# car_board_ver1.net
KiCad netlist of a schematic drawn in Altium Designer
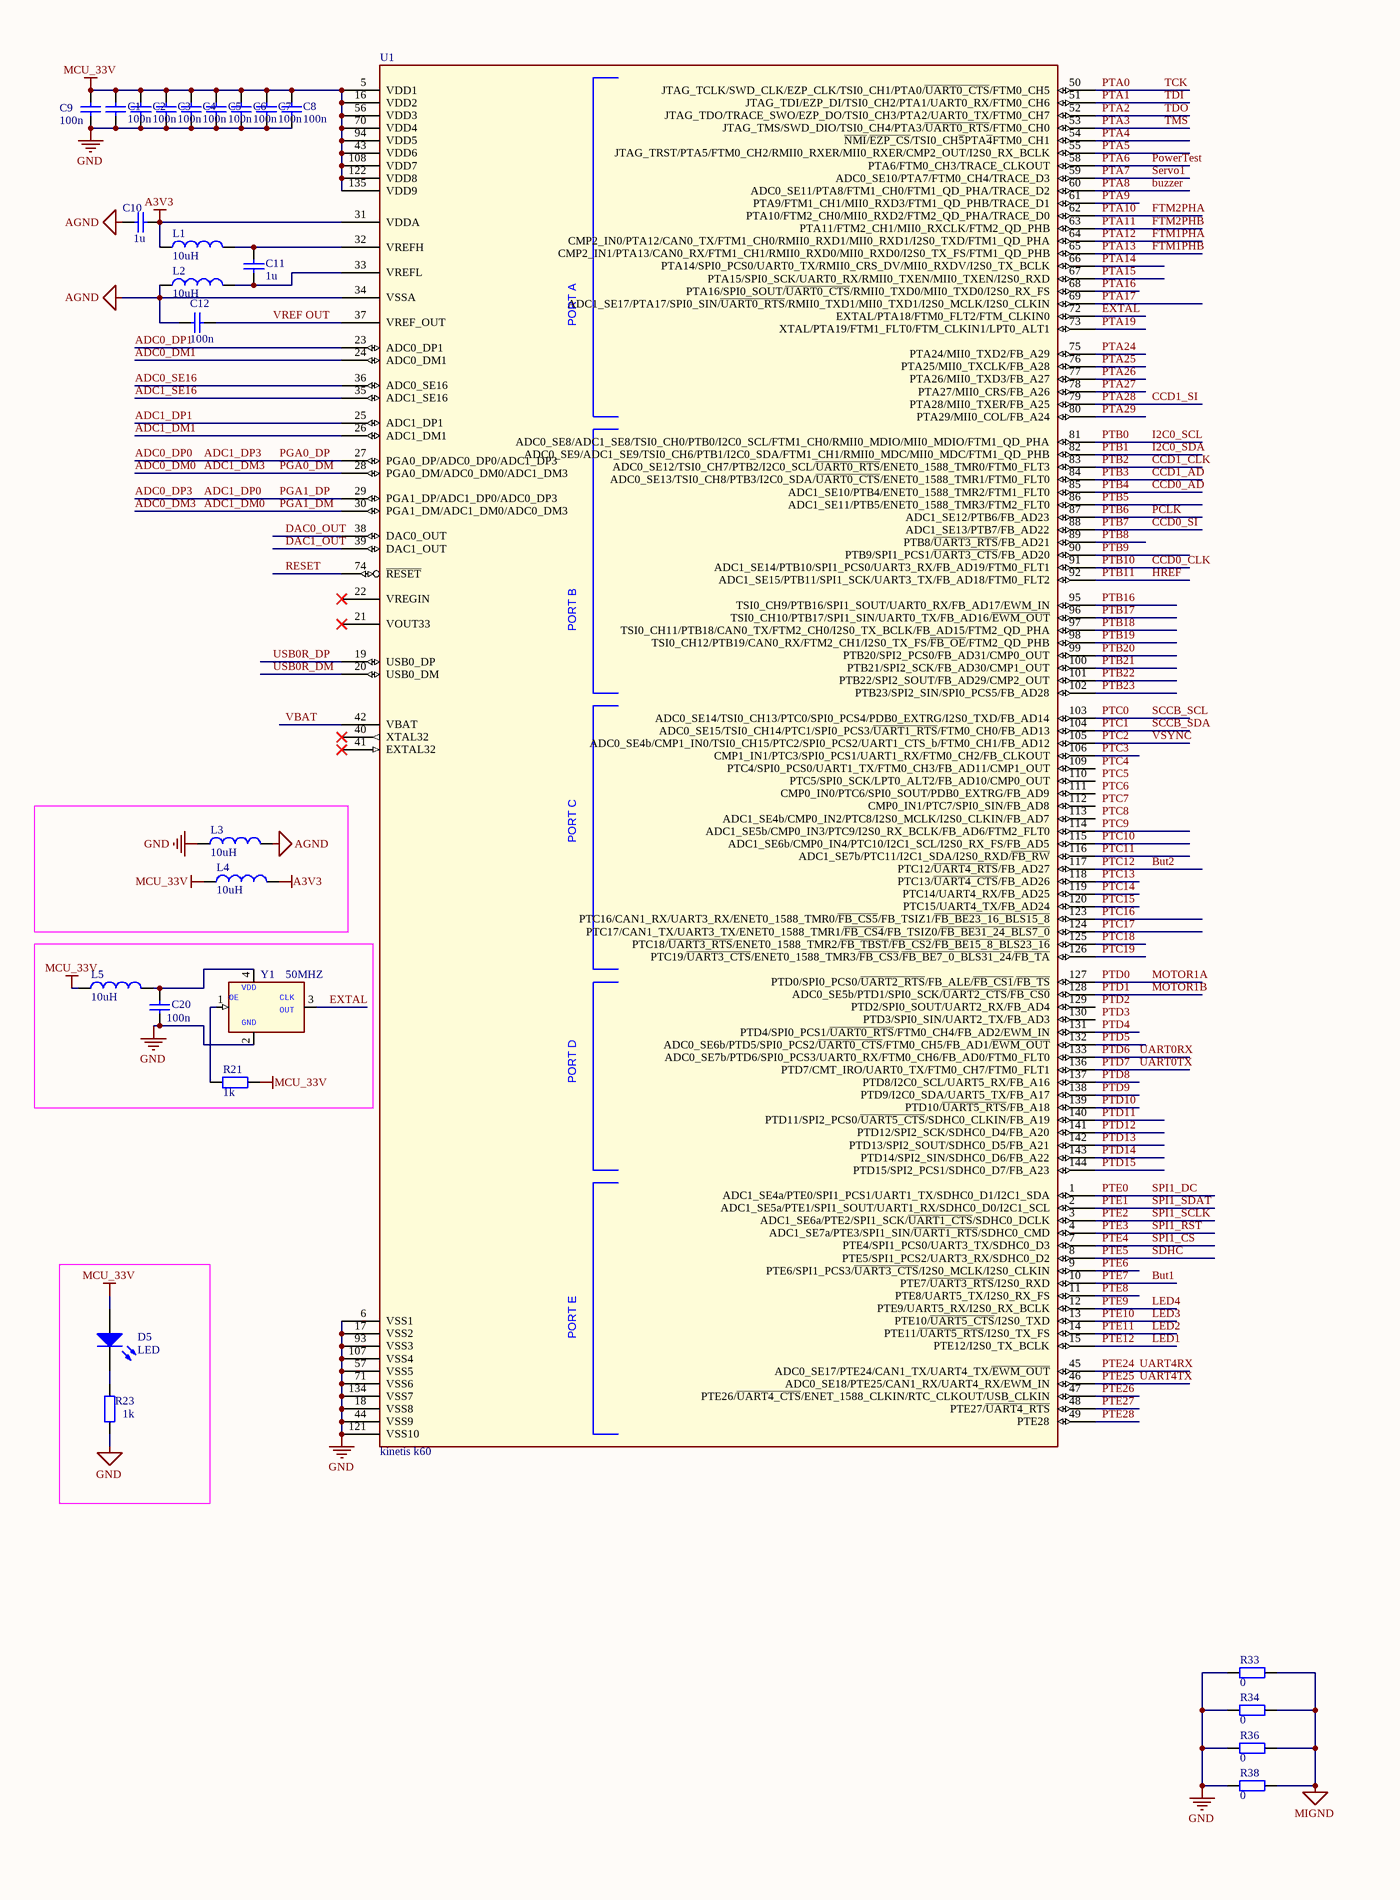
[diagram p0: car board ver1.SchDoc, left]
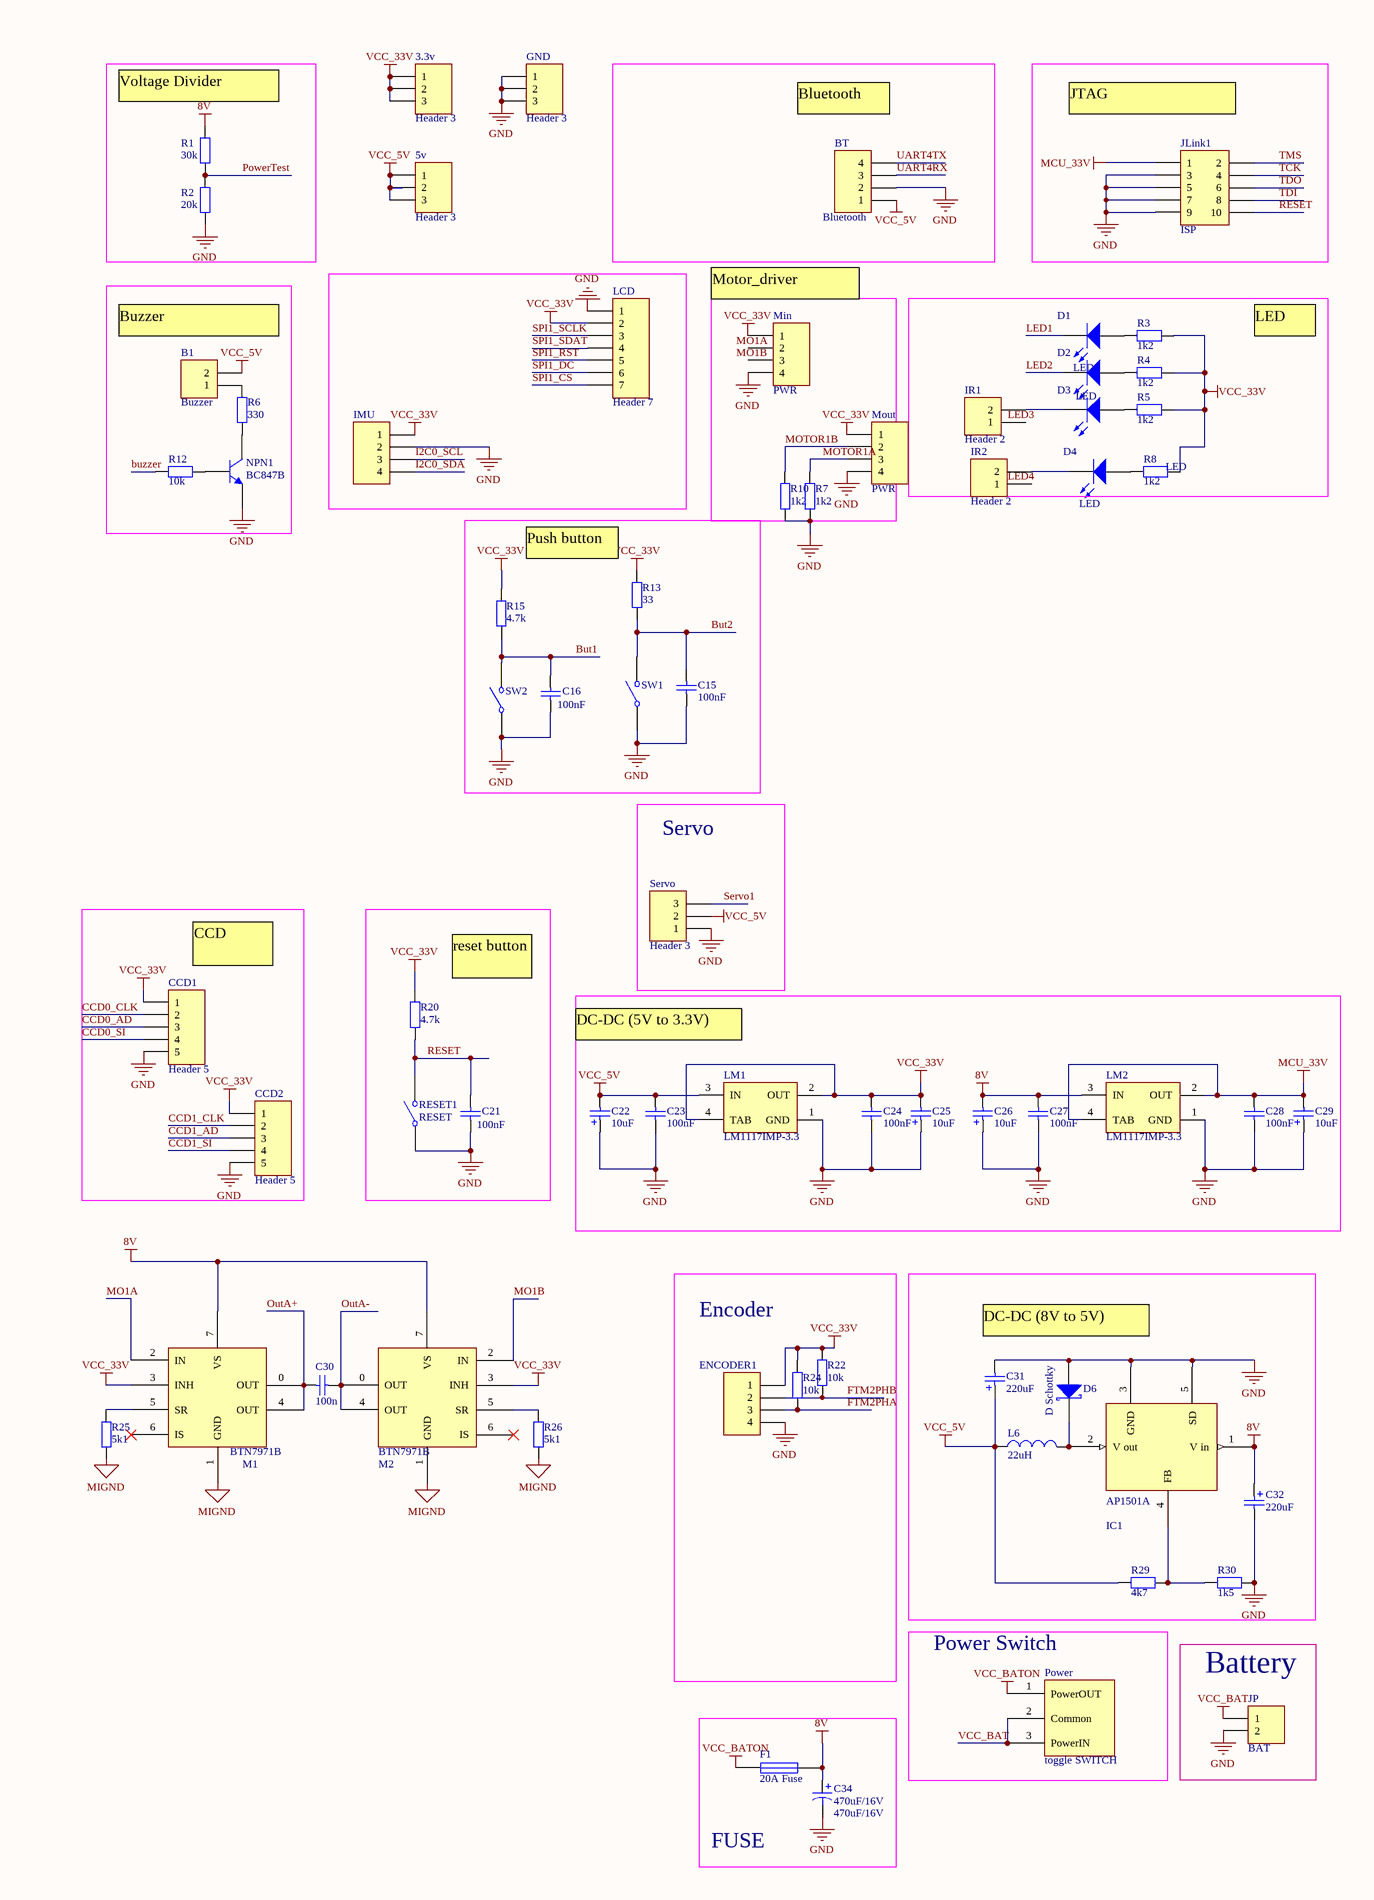
[diagram p1: car board ver1.SchDoc, right]

(export (version "E")
  (design (tool "Eeschema 10.0.6"))
  (components
    (comp (ref "3.3v")
      (value "Header 3")
      (footprint "HDR1X3")
      (description "Header, 3-Pin")
      (fields (field (name "PUBLISHER") "Altium Limited"))
      (libsource (lib "SmartCar2015_Connectors") (part "Header 3"))
    )
    (comp (ref "5v")
      (value "Header 3")
      (footprint "HDR1X3")
      (description "Header, 3-Pin")
      (fields (field (name "PUBLISHER") "Altium Limited"))
      (libsource (lib "SmartCar2015_Connectors") (part "Header 3"))
    )
    (comp (ref "B1")
      (value "Buzzer")
      (footprint "Buzzer")
      (libsource (lib "SmartCar2015_RCL") (part "Buzzer"))
    )
    (comp (ref "BT")
      (value "Bluetooth")
      (footprint "6410-04")
      (description "Header, 4-Pin")
      (fields (field (name "PUBLISHER") "Altium Limited"))
      (libsource (lib "") (part "Header 4_2"))
    )
    (comp (ref "C1")
      (value "100n")
      (footprint "CC2012-0805")
      (description "Capacitor (Semiconductor SIM Model)")
      (fields (field (name "PUBLISHER") "Altium Limited"))
      (libsource (lib "SmartCar2015_RCL") (part "Cap Semi"))
    )
    (comp (ref "C2")
      (value "100n")
      (footprint "CC2012-0805")
      (description "Capacitor (Semiconductor SIM Model)")
      (fields (field (name "PUBLISHER") "Altium Limited"))
      (libsource (lib "SmartCar2015_RCL") (part "Cap Semi"))
    )
    (comp (ref "C3")
      (value "100n")
      (footprint "CC2012-0805")
      (description "Capacitor (Semiconductor SIM Model)")
      (fields (field (name "PUBLISHER") "Altium Limited"))
      (libsource (lib "SmartCar2015_RCL") (part "Cap Semi"))
    )
    (comp (ref "C4")
      (value "100n")
      (footprint "CC2012-0805")
      (description "Capacitor (Semiconductor SIM Model)")
      (fields (field (name "PUBLISHER") "Altium Limited"))
      (libsource (lib "SmartCar2015_RCL") (part "Cap Semi"))
    )
    (comp (ref "C5")
      (value "100n")
      (footprint "CC2012-0805")
      (description "Capacitor (Semiconductor SIM Model)")
      (fields (field (name "PUBLISHER") "Altium Limited"))
      (libsource (lib "SmartCar2015_RCL") (part "Cap Semi"))
    )
    (comp (ref "C6")
      (value "100n")
      (footprint "CC2012-0805")
      (description "Capacitor (Semiconductor SIM Model)")
      (fields (field (name "PUBLISHER") "Altium Limited"))
      (libsource (lib "SmartCar2015_RCL") (part "Cap Semi"))
    )
    (comp (ref "C7")
      (value "100n")
      (footprint "CC2012-0805")
      (description "Capacitor (Semiconductor SIM Model)")
      (fields (field (name "PUBLISHER") "Altium Limited"))
      (libsource (lib "SmartCar2015_RCL") (part "Cap Semi"))
    )
    (comp (ref "C8")
      (value "100n")
      (footprint "CC2012-0805")
      (description "Capacitor (Semiconductor SIM Model)")
      (fields (field (name "PUBLISHER") "Altium Limited"))
      (libsource (lib "SmartCar2015_RCL") (part "Cap Semi"))
    )
    (comp (ref "C9")
      (value "100n")
      (footprint "CC2012-0805")
      (description "Capacitor (Semiconductor SIM Model)")
      (fields (field (name "PUBLISHER") "Altium Limited"))
      (libsource (lib "SmartCar2015_RCL") (part "Cap Semi"))
    )
    (comp (ref "C10")
      (value "1u")
      (footprint "CC2012-0805")
      (description "Capacitor (Semiconductor SIM Model)")
      (fields (field (name "PUBLISHER") "Altium Limited"))
      (libsource (lib "SmartCar2015_RCL") (part "Cap Semi"))
    )
    (comp (ref "C11")
      (value "1u")
      (footprint "CC2012-0805")
      (description "Capacitor (Semiconductor SIM Model)")
      (fields (field (name "PUBLISHER") "Altium Limited"))
      (libsource (lib "SmartCar2015_RCL") (part "Cap Semi"))
    )
    (comp (ref "C12")
      (value "100n")
      (footprint "CC2012-0805")
      (description "Capacitor (Semiconductor SIM Model)")
      (fields (field (name "PUBLISHER") "Altium Limited"))
      (libsource (lib "SmartCar2015_RCL") (part "Cap Semi"))
    )
    (comp (ref "C15")
      (value "100nF")
      (footprint "CC2012-0805")
      (description "Capacitor (Semiconductor SIM Model)")
      (fields (field (name "PUBLISHER") "Altium Limited"))
      (libsource (lib "SmartCar2015_RCL") (part "Cap Semi"))
    )
    (comp (ref "C16")
      (value "100nF")
      (footprint "CC2012-0805")
      (description "Capacitor (Semiconductor SIM Model)")
      (fields (field (name "PUBLISHER") "Altium Limited"))
      (libsource (lib "SmartCar2015_RCL") (part "Cap Semi"))
    )
    (comp (ref "C20")
      (value "100n")
      (footprint "CC2012-0805")
      (description "Capacitor (Semiconductor SIM Model)")
      (fields (field (name "PUBLISHER") "Altium Limited"))
      (libsource (lib "SmartCar2015_RCL") (part "Cap Semi"))
    )
    (comp (ref "C21")
      (value "100nF")
      (footprint "CC2012-0805")
      (description "Capacitor (Semiconductor SIM Model)")
      (fields (field (name "PUBLISHER") "Altium Limited"))
      (libsource (lib "SmartCar2015_RCL") (part "Cap Semi"))
    )
    (comp (ref "C22")
      (value "10uF")
      (footprint "CC2012-0805")
      (description "Polarized Capacitor (Surface Mount)")
      (fields (field (name "PUBLISHER") "Altium Limited"))
      (libsource (lib "SmartCar2015_RCL") (part "Cap Pol3"))
    )
    (comp (ref "C23")
      (value "100nF")
      (footprint "CC2012-0805")
      (description "Capacitor (Semiconductor SIM Model)")
      (fields (field (name "PUBLISHER") "Altium Limited"))
      (libsource (lib "SmartCar2015_RCL") (part "Cap Semi"))
    )
    (comp (ref "C24")
      (value "100nF")
      (footprint "CC2012-0805")
      (description "Capacitor (Semiconductor SIM Model)")
      (fields (field (name "PUBLISHER") "Altium Limited"))
      (libsource (lib "SmartCar2015_RCL") (part "Cap Semi"))
    )
    (comp (ref "C25")
      (value "10uF")
      (footprint "CC2012-0805")
      (description "Polarized Capacitor (Surface Mount)")
      (fields (field (name "PUBLISHER") "Altium Limited"))
      (libsource (lib "SmartCar2015_RCL") (part "Cap Pol3"))
    )
    (comp (ref "C26")
      (value "10uF")
      (footprint "CC2012-0805")
      (description "Polarized Capacitor (Surface Mount)")
      (fields (field (name "PUBLISHER") "Altium Limited"))
      (libsource (lib "SmartCar2015_RCL") (part "Cap Pol3"))
    )
    (comp (ref "C27")
      (value "100nF")
      (footprint "CC2012-0805")
      (description "Capacitor (Semiconductor SIM Model)")
      (fields (field (name "PUBLISHER") "Altium Limited"))
      (libsource (lib "SmartCar2015_RCL") (part "Cap Semi"))
    )
    (comp (ref "C28")
      (value "100nF")
      (footprint "CC2012-0805")
      (description "Capacitor (Semiconductor SIM Model)")
      (fields (field (name "PUBLISHER") "Altium Limited"))
      (libsource (lib "SmartCar2015_RCL") (part "Cap Semi"))
    )
    (comp (ref "C29")
      (value "10uF")
      (footprint "CC2012-0805")
      (description "Polarized Capacitor (Surface Mount)")
      (fields (field (name "PUBLISHER") "Altium Limited"))
      (libsource (lib "SmartCar2015_RCL") (part "Cap Pol3"))
    )
    (comp (ref "C30")
      (value "100n")
      (footprint "CC2012-0805")
      (description "Capacitor")
      (fields (field (name "PUBLISHER") "Altium Limited"))
      (libsource (lib "SmartCar2015_RCL") (part "Cap"))
    )
    (comp (ref "C31")
      (value "220uF")
      (footprint "CAPC7238N")
      (description "Polarized Capacitor (Radial)")
      (fields (field (name "PUBLISHER") "Altium Limited"))
      (libsource (lib "SmartCar2015_RCL") (part "Cap Pol1"))
    )
    (comp (ref "C32")
      (value "220uF")
      (footprint "CAPC7238N")
      (description "Polarized Capacitor (Radial)")
      (fields (field (name "PUBLISHER") "Altium Limited"))
      (libsource (lib "SmartCar2015_RCL") (part "Cap Pol1"))
    )
    (comp (ref "C34")
      (value "470uF/16V")
      (footprint "SV-G")
      (description "Polarized Capacitor (Axial)")
      (fields (field (name "ALTIUM_VALUE") "470uF/16V") (field (name "PUBLISHER") "Altium Limited"))
      (libsource (lib "SmartCar2015_RCL") (part "Cap Pol2"))
    )
    (comp (ref "CCD1")
      (value "Header 5")
      (footprint "HDR1X5")
      (description "Header, 5-Pin")
      (fields (field (name "PUBLISHER") "Altium Limited"))
      (libsource (lib "SmartCar2015_Connectors") (part "Header 5"))
    )
    (comp (ref "CCD2")
      (value "Header 5")
      (footprint "HDR1X5")
      (description "Header, 5-Pin")
      (fields (field (name "PUBLISHER") "Altium Limited"))
      (libsource (lib "SmartCar2015_Connectors") (part "Header 5"))
    )
    (comp (ref "D1")
      (value "LED")
      (footprint "SMD _LED")
      (description "Typical RED GaAs LED")
      (fields (field (name "PUBLISHER") "Altium Limited"))
      (libsource (lib "SmartCar2015_BJT") (part "LED"))
    )
    (comp (ref "D2")
      (value "LED")
      (footprint "SMD _LED")
      (description "Typical RED GaAs LED")
      (fields (field (name "PUBLISHER") "Altium Limited"))
      (libsource (lib "SmartCar2015_BJT") (part "LED"))
    )
    (comp (ref "D3")
      (value "LED")
      (footprint "SMD _LED")
      (description "Typical RED GaAs LED")
      (fields (field (name "PUBLISHER") "Altium Limited"))
      (libsource (lib "SmartCar2015_BJT") (part "LED"))
    )
    (comp (ref "D4")
      (value "LED")
      (footprint "SMD _LED")
      (description "Typical RED GaAs LED")
      (fields (field (name "PUBLISHER") "Altium Limited"))
      (libsource (lib "SmartCar2015_BJT") (part "LED"))
    )
    (comp (ref "D5")
      (value "LED")
      (footprint "SMD _LED")
      (description "Typical RED GaAs LED")
      (fields (field (name "PUBLISHER") "Altium Limited"))
      (libsource (lib "SmartCar2015_BJT") (part "LED"))
    )
    (comp (ref "D6")
      (value "D Schottky")
      (footprint "SMC")
      (description "Schottky Diode")
      (fields (field (name "PUBLISHER") "Altium Limited"))
      (libsource (lib "SmartCar2015_BJT") (part "D Schottky"))
    )
    (comp (ref "ENCODER1")
      (value "~")
      (footprint "6410-04")
      (description "Header, 4-Pin")
      (fields (field (name "PUBLISHER") "Altium Limited"))
      (libsource (lib "SmartCar2015_Connectors") (part "Header 4"))
    )
    (comp (ref "F1")
      (value "20A Fuse")
      (footprint "FUSE")
      (description "Fuse")
      (fields (field (name "PUBLISHER") "Altium Limited"))
      (libsource (lib "SmartCar2015_Connectors") (part "Fuse"))
    )
    (comp (ref "GND")
      (value "Header 3")
      (footprint "HDR1X3")
      (description "Header, 3-Pin")
      (fields (field (name "PUBLISHER") "Altium Limited"))
      (libsource (lib "SmartCar2015_Connectors") (part "Header 3"))
    )
    (comp (ref "IC1")
      (value "AP1501A")
      (footprint "TO-263(5)")
      (description "5A Step-Down Switching Mode Voltage Regulator")
      (libsource (lib "Smartcar_2014_ICs") (part "AP1501A"))
    )
    (comp (ref "IMU")
      (value "~")
      (footprint "6410-04")
      (description "Header, 4-Pin")
      (fields (field (name "PUBLISHER") "Altium Limited"))
      (libsource (lib "SmartCar2015_Connectors") (part "Header 4"))
    )
    (comp (ref "IR1")
      (value "Header 2")
      (footprint "6410-02")
      (description "Header, 2-Pin")
      (fields (field (name "PUBLISHER") "Altium Limited"))
      (libsource (lib "SmartCar2015_Connectors") (part "Header 2"))
    )
    (comp (ref "IR2")
      (value "Header 2")
      (footprint "6410-02")
      (description "Header, 2-Pin")
      (fields (field (name "PUBLISHER") "Altium Limited"))
      (libsource (lib "SmartCar2015_Connectors") (part "Header 2"))
    )
    (comp (ref "JLink1")
      (value "ISP")
      (footprint "HDR2X5")
      (description "Header, 5-Pin, Dual row")
      (fields (field (name "PUBLISHER") "Altium Limited"))
      (libsource (lib "SmartCar2015_Connectors") (part "Header 5X2"))
    )
    (comp (ref "JP")
      (value "BAT")
      (footprint "T-CONNECTOR (M)")
      (description "Header, 2-Pin")
      (fields (field (name "PUBLISHER") "Altium Limited"))
      (libsource (lib "T head 2") (part "Header 2"))
    )
    (comp (ref "L1")
      (value "10uH")
      (footprint "CR3225-1210")
      (description "Inductor")
      (fields (field (name "PUBLISHER") "Altium Limited"))
      (libsource (lib "SmartCar2015_RCL") (part "Inductor"))
    )
    (comp (ref "L2")
      (value "10uH")
      (footprint "CR3225-1210")
      (description "Inductor")
      (fields (field (name "PUBLISHER") "Altium Limited"))
      (libsource (lib "SmartCar2015_RCL") (part "Inductor"))
    )
    (comp (ref "L3")
      (value "10uH")
      (footprint "CR3225-1210")
      (description "Inductor")
      (fields (field (name "PUBLISHER") "Altium Limited"))
      (libsource (lib "SmartCar2015_RCL") (part "Inductor"))
    )
    (comp (ref "L4")
      (value "10uH")
      (footprint "CR3225-1210")
      (description "Inductor")
      (fields (field (name "PUBLISHER") "Altium Limited"))
      (libsource (lib "SmartCar2015_RCL") (part "Inductor"))
    )
    (comp (ref "L5")
      (value "10uH")
      (footprint "CR3225-1210")
      (description "Inductor")
      (fields (field (name "PUBLISHER") "Altium Limited"))
      (libsource (lib "SmartCar2015_RCL") (part "Inductor"))
    )
    (comp (ref "L6")
      (value "22uH")
      (footprint "CR3225-1210")
      (description "Inductor")
      (fields (field (name "PUBLISHER") "Altium Limited"))
      (libsource (lib "SmartCar2015_RCL") (part "Inductor"))
    )
    (comp (ref "LCD")
      (value "Header 7")
      (footprint "HDR1X7")
      (description "Header, 7-Pin")
      (fields (field (name "PUBLISHER") "Altium Limited"))
      (libsource (lib "SmartCar2015_Connectors") (part "Header 7"))
    )
    (comp (ref "LM1")
      (value "LM1117IMP-3.3")
      (footprint "MP04A_M")
      (description "800mA Low-Dropout Linear Regulator")
      (fields
        (field (name "MANUFACTURER") "National Semiconductor")
        (field (name "DIGIKEYPARTNUMBER") "LM1117IMP-3.3CT-ND")
        (field (name "PUBLISHER") "Altium Limited")
      )
      (libsource (lib "NSC LDO") (part "LM1117IMP-3.3"))
    )
    (comp (ref "LM2")
      (value "LM1117IMP-3.3")
      (footprint "MP04A_M")
      (description "800mA Low-Dropout Linear Regulator")
      (fields
        (field (name "MANUFACTURER") "National Semiconductor")
        (field (name "DIGIKEYPARTNUMBER") "LM1117IMP-3.3CT-ND")
        (field (name "PUBLISHER") "Altium Limited")
      )
      (libsource (lib "NSC LDO") (part "LM1117IMP-3.3"))
    )
    (comp (ref "M1")
      (value "BTN7971B")
      (footprint "TO-263(7)")
      (libsource (lib "Smartcar_2014_ICs") (part "BTS 7970B"))
    )
    (comp (ref "M2") (value "BTN7971B") (footprint "TO-263(7)") (libsource (lib "") (part "BTS 7970B_1")))
    (comp (ref "Min")
      (value "PWR")
      (footprint "HDR1X4")
      (description "Header, 4-Pin")
      (fields (field (name "PUBLISHER") "Altium Limited"))
      (libsource (lib "") (part "Header 4_1"))
    )
    (comp (ref "Mout")
      (value "PWR")
      (footprint "HDR1X4")
      (description "Header, 4-Pin")
      (fields (field (name "PUBLISHER") "Altium Limited"))
      (libsource (lib "") (part "Header 4_1"))
    )
    (comp (ref "NPN1")
      (value "BC847B")
      (footprint "SOT-23")
      (description "NPN")
      (libsource (lib "SmartCar2015_BJT") (part "BC847B"))
    )
    (comp (ref "Power")
      (value "toggle SWITCH")
      (footprint "ToggleSwitch")
      (libsource (lib "AltiumLib1") (part "toggle SWITCH"))
    )
    (comp (ref "R1")
      (value "30k")
      (footprint "CR2012-0805")
      (description "Resistor")
      (fields (field (name "PUBLISHER") "Altium Limited"))
      (libsource (lib "") (part "Res2_1"))
    )
    (comp (ref "R2")
      (value "20k")
      (footprint "CR2012-0805")
      (description "Resistor")
      (fields (field (name "PUBLISHER") "Altium Limited"))
      (libsource (lib "") (part "Res2_1"))
    )
    (comp (ref "R3")
      (value "1k2")
      (footprint "CR2012-0805")
      (description "Resistor")
      (fields (field (name "PUBLISHER") "Altium Limited"))
      (libsource (lib "SmartCar2015_RCL") (part "Res2"))
    )
    (comp (ref "R4")
      (value "1k2")
      (footprint "CR2012-0805")
      (description "Resistor")
      (fields (field (name "PUBLISHER") "Altium Limited"))
      (libsource (lib "SmartCar2015_RCL") (part "Res2"))
    )
    (comp (ref "R5")
      (value "1k2")
      (footprint "CR2012-0805")
      (description "Resistor")
      (fields (field (name "PUBLISHER") "Altium Limited"))
      (libsource (lib "SmartCar2015_RCL") (part "Res2"))
    )
    (comp (ref "R6")
      (value "330")
      (footprint "CR2012-0805")
      (description "Resistor")
      (fields (field (name "PUBLISHER") "Altium Limited"))
      (libsource (lib "") (part "Res2_2"))
    )
    (comp (ref "R7")
      (value "1k2")
      (footprint "CR2012-0805")
      (description "Resistor")
      (fields (field (name "PUBLISHER") "Altium Limited"))
      (libsource (lib "") (part "Res2_1"))
    )
    (comp (ref "R8")
      (value "1k2")
      (footprint "CR2012-0805")
      (description "Resistor")
      (fields (field (name "PUBLISHER") "Altium Limited"))
      (libsource (lib "SmartCar2015_RCL") (part "Res2"))
    )
    (comp (ref "R10")
      (value "1k2")
      (footprint "CR2012-0805")
      (description "Resistor")
      (fields (field (name "PUBLISHER") "Altium Limited"))
      (libsource (lib "") (part "Res2_1"))
    )
    (comp (ref "R12")
      (value "10k")
      (footprint "CR2012-0805")
      (description "Resistor")
      (fields (field (name "PUBLISHER") "Altium Limited"))
      (libsource (lib "SmartCar2015_RCL") (part "Res2"))
    )
    (comp (ref "R13")
      (value "33")
      (footprint "CR2012-0805")
      (description "Resistor")
      (fields (field (name "PUBLISHER") "Altium Limited"))
      (libsource (lib "") (part "Res2_2"))
    )
    (comp (ref "R15")
      (value "4.7k")
      (footprint "CR2012-0805")
      (description "Resistor")
      (fields (field (name "Comment") "4k7") (field (name "PUBLISHER") "Altium Limited"))
      (libsource (lib "") (part "Res2_2"))
    )
    (comp (ref "R20")
      (value "4.7k")
      (footprint "CR2012-0805")
      (description "Resistor")
      (fields (field (name "Comment") "4k7") (field (name "PUBLISHER") "Altium Limited"))
      (libsource (lib "") (part "Res2_2"))
    )
    (comp (ref "R21")
      (value "1k")
      (footprint "CR2012-0805")
      (description "Resistor")
      (fields (field (name "PUBLISHER") "Altium Limited"))
      (libsource (lib "SmartCar2015_RCL") (part "Res2"))
    )
    (comp (ref "R22")
      (value "10k")
      (footprint "CR2012-0805")
      (description "Resistor")
      (fields (field (name "PUBLISHER") "Altium Limited"))
      (libsource (lib "") (part "Res2_1"))
    )
    (comp (ref "R23")
      (value "1k")
      (footprint "CR2012-0805")
      (description "Resistor")
      (fields (field (name "PUBLISHER") "Altium Limited"))
      (libsource (lib "") (part "Res2_2"))
    )
    (comp (ref "R24")
      (value "10k")
      (footprint "CR2012-0805")
      (description "Resistor")
      (fields (field (name "PUBLISHER") "Altium Limited"))
      (libsource (lib "") (part "Res2_1"))
    )
    (comp (ref "R25")
      (value "5k1")
      (footprint "CR2012-0805")
      (description "Resistor")
      (fields (field (name "PUBLISHER") "Altium Limited"))
      (libsource (lib "") (part "Res2_1"))
    )
    (comp (ref "R26")
      (value "5k1")
      (footprint "CR2012-0805")
      (description "Resistor")
      (fields (field (name "PUBLISHER") "Altium Limited"))
      (libsource (lib "") (part "Res2_1"))
    )
    (comp (ref "R29")
      (value "4k7")
      (footprint "CR2012-0805")
      (description "Resistor")
      (fields (field (name "PUBLISHER") "Altium Limited"))
      (libsource (lib "SmartCar2015_RCL") (part "Res2"))
    )
    (comp (ref "R30")
      (value "1k5")
      (footprint "CR2012-0805")
      (description "Resistor")
      (fields (field (name "PUBLISHER") "Altium Limited"))
      (libsource (lib "SmartCar2015_RCL") (part "Res2"))
    )
    (comp (ref "R33")
      (value "0")
      (footprint "CR2012-0805")
      (description "Resistor")
      (fields (field (name "PUBLISHER") "Altium Limited"))
      (libsource (lib "SmartCar2015_RCL") (part "Res2"))
    )
    (comp (ref "R34")
      (value "0")
      (footprint "CR2012-0805")
      (description "Resistor")
      (fields (field (name "PUBLISHER") "Altium Limited"))
      (libsource (lib "SmartCar2015_RCL") (part "Res2"))
    )
    (comp (ref "R36")
      (value "0")
      (footprint "CR2012-0805")
      (description "Resistor")
      (fields (field (name "PUBLISHER") "Altium Limited"))
      (libsource (lib "SmartCar2015_RCL") (part "Res2"))
    )
    (comp (ref "R38")
      (value "0")
      (footprint "CR2012-0805")
      (description "Resistor")
      (fields (field (name "PUBLISHER") "Altium Limited"))
      (libsource (lib "SmartCar2015_RCL") (part "Res2"))
    )
    (comp (ref "RESET1")
      (value "RESET")
      (footprint "PUSHBUTTOM")
      (description "Single-Pole, Single-Throw Switch")
      (fields (field (name "PUBLISHER") "Altium Limited"))
      (libsource (lib "SmartCar2015_Connectors") (part "SW-SPST"))
    )
    (comp (ref "Servo")
      (value "Header 3")
      (footprint "6410-03")
      (description "Header, 3-Pin")
      (fields (field (name "PUBLISHER") "Altium Limited"))
      (libsource (lib "") (part "Header 3_1"))
    )
    (comp (ref "SW1")
      (value "~")
      (footprint "PUSHBUTTOM")
      (description "Single-Pole, Single-Throw Switch")
      (fields (field (name "PUBLISHER") "Altium Limited"))
      (libsource (lib "SmartCar2015_Connectors") (part "SW-SPST"))
    )
    (comp (ref "SW2")
      (value "~")
      (footprint "PUSHBUTTOM")
      (description "Single-Pole, Single-Throw Switch")
      (fields (field (name "PUBLISHER") "Altium Limited"))
      (libsource (lib "Robocn_connectors 2") (part "SW-SPST"))
    )
    (comp (ref "U1")
      (value "kinetis k60")
      (footprint "LQFP50P2200X2200X160-144M")
      (libsource (lib "Smartcar_IC") (part "kinetis k60"))
    )
    (comp (ref "Y1") (value "50MHZ") (footprint "XTLOSC4_SM") (libsource (lib "SmartCar") (part "CLKGEN-SM")))
  )
  (nets
    (net (code "1") (name "/ADC0_DM0") (class "Default")
      (node (ref "U1") (pin "28") (pinfunction "PGA0_DM/ADC0_DM0/ADC1_DM3_28") (pintype "bidirectional"))
    )
    (net (code "2") (name "/ADC0_DM1") (class "Default")
      (node (ref "U1") (pin "24") (pinfunction "ADC0_DM1_24") (pintype "bidirectional"))
    )
    (net (code "3") (name "/ADC0_DM3") (class "Default")
      (node (ref "U1") (pin "30") (pinfunction "PGA1_DM/ADC1_DM0/ADC0_DM3_30") (pintype "bidirectional"))
    )
    (net (code "4") (name "/ADC0_DP0") (class "Default")
      (node (ref "U1") (pin "27") (pinfunction "PGA0_DP/ADC0_DP0/ADC1_DP3_27") (pintype "bidirectional"))
    )
    (net (code "5") (name "/ADC0_DP1") (class "Default")
      (node (ref "U1") (pin "23") (pinfunction "ADC0_DP1_23") (pintype "bidirectional"))
    )
    (net (code "6") (name "/ADC0_DP3") (class "Default")
      (node (ref "U1") (pin "29") (pinfunction "PGA1_DP/ADC1_DP0/ADC0_DP3_29") (pintype "bidirectional"))
    )
    (net (code "7") (name "/ADC0_SE16") (class "Default")
      (node (ref "U1") (pin "36") (pinfunction "ADC0_SE16_36") (pintype "bidirectional"))
    )
    (net (code "8") (name "/ADC1_DM1") (class "Default")
      (node (ref "U1") (pin "26") (pinfunction "ADC1_DM1_26") (pintype "bidirectional"))
    )
    (net (code "9") (name "/ADC1_DP1") (class "Default")
      (node (ref "U1") (pin "25") (pinfunction "ADC1_DP1_25") (pintype "bidirectional"))
    )
    (net (code "10") (name "/ADC1_SE16") (class "Default")
      (node (ref "U1") (pin "35") (pinfunction "ADC1_SE16_35") (pintype "bidirectional"))
    )
    (net (code "11") (name "/But1") (class "Default")
      (node (ref "C16") (pin "2") (pinfunction "2_2") (pintype "passive"))
      (node (ref "R15") (pin "2") (pinfunction "2_2") (pintype "passive"))
      (node (ref "SW2") (pin "2") (pinfunction "NO_2") (pintype "passive"))
      (node (ref "U1") (pin "10") (pinfunction "PTE7/~{UART3_RTS}/I2S0_RXD_10") (pintype "bidirectional"))
    )
    (net (code "12") (name "/But2") (class "Default")
      (node (ref "C15") (pin "2") (pinfunction "2_2") (pintype "passive"))
      (node (ref "R13") (pin "2") (pinfunction "2_2") (pintype "passive"))
      (node (ref "SW1") (pin "2") (pinfunction "NO_2") (pintype "passive"))
      (node (ref "U1") (pin "117") (pinfunction "PTC12/~{UART4_RTS}/FB_AD27_117") (pintype "bidirectional"))
    )
    (net (code "13") (name "/CCD0_AD") (class "Default")
      (node (ref "CCD1") (pin "3") (pinfunction "3_3") (pintype "passive"))
      (node (ref "U1") (pin "85") (pinfunction "ADC1_SE10/PTB4/ENET0_1588_TMR2/FTM1_FLT0_85") (pintype "bidirectional"))
    )
    (net (code "14") (name "/CCD0_CLK") (class "Default")
      (node (ref "CCD1") (pin "2") (pinfunction "2_2") (pintype "passive"))
      (node (ref "U1") (pin "91") (pinfunction "ADC1_SE14/PTB10/SPI1_PCS0/UART3_RX/FB_AD19/FTM0_FLT1_91") (pintype "bidirectional"))
    )
    (net (code "15") (name "/CCD0_SI") (class "Default")
      (node (ref "CCD1") (pin "4") (pinfunction "4_4") (pintype "passive"))
      (node (ref "U1") (pin "88") (pinfunction "ADC1_SE13/PTB7/FB_AD22_88") (pintype "bidirectional"))
    )
    (net (code "16") (name "/CCD1_AD") (class "Default")
      (node (ref "CCD2") (pin "3") (pinfunction "3_3") (pintype "passive"))
      (node (ref "U1") (pin "84") (pinfunction "ADC0_SE13/TSI0_CH8/PTB3/I2C0_SDA/~{UART0_CTS}/ENET0_1588_TMR1/FTM0_FLT0_84") (pintype "bidirectional"))
    )
    (net (code "17") (name "/CCD1_CLK") (class "Default")
      (node (ref "CCD2") (pin "2") (pinfunction "2_2") (pintype "passive"))
      (node (ref "U1") (pin "83") (pinfunction "ADC0_SE12/TSI0_CH7/PTB2/I2C0_SCL/~{UART0_RTS}/ENET0_1588_TMR0/FTM0_FLT3_83") (pintype "bidirectional"))
    )
    (net (code "18") (name "/CCD1_SI") (class "Default")
      (node (ref "CCD2") (pin "4") (pinfunction "4_4") (pintype "passive"))
      (node (ref "U1") (pin "79") (pinfunction "PTA28/MII0_TXER/FB_A25_79") (pintype "bidirectional"))
    )
    (net (code "19") (name "/DAC0_OUT") (class "Default")
      (node (ref "U1") (pin "38") (pinfunction "DAC0_OUT_38") (pintype "bidirectional"))
    )
    (net (code "20") (name "/DAC1_OUT") (class "Default")
      (node (ref "U1") (pin "39") (pinfunction "DAC1_OUT_39") (pintype "bidirectional"))
    )
    (net (code "21") (name "/EXTAL") (class "Default")
      (node (ref "U1") (pin "72") (pinfunction "EXTAL/PTA18/FTM0_FLT2/FTM_CLKIN0_72") (pintype "bidirectional"))
      (node (ref "Y1") (pin "3") (pinfunction "CLKOUT_3") (pintype "tri_state"))
    )
    (net (code "22") (name "/FTM1PHA") (class "Default")
      (node (ref "U1") (pin "64") (pinfunction "CMP2_IN0/PTA12/CAN0_TX/FTM1_CH0/RMII0_RXD1/MII0_RXD1/I2S0_TXD/FTM1_QD_PHA_64") (pintype "bidirectional"))
    )
    (net (code "23") (name "/FTM1PHB") (class "Default")
      (node (ref "U1") (pin "65") (pinfunction "CMP2_IN1/PTA13/CAN0_RX/FTM1_CH1/RMII0_RXD0/MII0_RXD0/I2S0_TX_FS/FTM1_QD_PHB_65") (pintype "bidirectional"))
    )
    (net (code "24") (name "/FTM2PHA") (class "Default")
      (node (ref "ENCODER1") (pin "3") (pinfunction "3_3") (pintype "passive"))
      (node (ref "R24") (pin "1") (pinfunction "1_1") (pintype "passive"))
      (node (ref "U1") (pin "62") (pinfunction "PTA10/FTM2_CH0/MII0_RXD2/FTM2_QD_PHA/TRACE_D0_62") (pintype "bidirectional"))
    )
    (net (code "25") (name "/FTM2PHB") (class "Default")
      (node (ref "ENCODER1") (pin "2") (pinfunction "2_2") (pintype "passive"))
      (node (ref "R22") (pin "1") (pinfunction "1_1") (pintype "passive"))
      (node (ref "U1") (pin "63") (pinfunction "PTA11/FTM2_CH1/MII0_RXCLK/FTM2_QD_PHB_63") (pintype "bidirectional"))
    )
    (net (code "26") (name "/HREF") (class "Default")
      (node (ref "U1") (pin "92") (pinfunction "ADC1_SE15/PTB11/SPI1_SCK/UART3_TX/FB_AD18/FTM0_FLT2_92") (pintype "bidirectional"))
    )
    (net (code "27") (name "/I2C0_SCL") (class "Default")
      (node (ref "IMU") (pin "3") (pinfunction "3_3") (pintype "passive"))
      (node (ref "U1") (pin "81") (pinfunction "ADC0_SE8/ADC1_SE8/TSI0_CH0/PTB0/I2C0_SCL/FTM1_CH0/RMII0_MDIO/MII0_MDIO/FTM1_QD_PHA_81") (pintype "bidirectional"))
    )
    (net (code "28") (name "/I2C0_SDA") (class "Default")
      (node (ref "IMU") (pin "4") (pinfunction "4_4") (pintype "passive"))
      (node (ref "U1") (pin "82") (pinfunction "ADC0_SE9/ADC1_SE9/TSI0_CH6/PTB1/I2C0_SDA/FTM1_CH1/RMII0_MDC/MII0_MDC/FTM1_QD_PHB_82") (pintype "bidirectional"))
    )
    (net (code "29") (name "/LED1") (class "Default")
      (node (ref "D1") (pin "2") (pinfunction "K_2") (pintype "passive"))
      (node (ref "U1") (pin "15") (pinfunction "PTE12/I2S0_TX_BCLK_15") (pintype "bidirectional"))
    )
    (net (code "30") (name "/LED2") (class "Default")
      (node (ref "D2") (pin "2") (pinfunction "K_2") (pintype "passive"))
      (node (ref "U1") (pin "14") (pinfunction "PTE11/~{UART5_RTS}/I2S0_TX_FS_14") (pintype "bidirectional"))
    )
    (net (code "31") (name "/LED3") (class "Default")
      (node (ref "U1") (pin "13") (pinfunction "PTE10/~{UART5_CTS}/I2S0_TXD_13") (pintype "bidirectional"))
    )
    (net (code "32") (name "/LED4") (class "Default")
      (node (ref "U1") (pin "12") (pinfunction "PTE9/UART5_RX/I2S0_RX_BCLK_12") (pintype "bidirectional"))
    )
    (net (code "33") (name "/MO1A") (class "Default")
      (node (ref "M1") (pin "2") (pinfunction "IN_2") (pintype "passive"))
    )
    (net (code "34") (name "/MO1B") (class "Default")
      (node (ref "M2") (pin "2") (pinfunction "IN_2") (pintype "passive"))
    )
    (net (code "35") (name "/MOTOR1A") (class "Default")
      (node (ref "Mout") (pin "3") (pinfunction "3_3") (pintype "passive"))
      (node (ref "R7") (pin "2") (pinfunction "2_2") (pintype "passive"))
      (node (ref "U1") (pin "127") (pinfunction "PTD0/SPI0_PCS0/~{UART2_RTS}/FB_ALE/~{FB_CS1}/~{FB_TS}_127") (pintype "bidirectional"))
    )
    (net (code "36") (name "/MOTOR1B") (class "Default")
      (node (ref "Mout") (pin "2") (pinfunction "2_2") (pintype "passive"))
      (node (ref "R10") (pin "2") (pinfunction "2_2") (pintype "passive"))
      (node (ref "U1") (pin "128") (pinfunction "ADC0_SE5b/PTD1/SPI0_SCK/~{UART2_CTS}/~{FB_CS0}_128") (pintype "bidirectional"))
    )
    (net (code "37") (name "/OutA+") (class "Default")
      (node (ref "C30") (pin "1") (pinfunction "1_1") (pintype "passive"))
      (node (ref "M1") (pin "0") (pinfunction "OUT_0") (pintype "passive"))
      (node (ref "M1") (pin "4") (pinfunction "OUT_4") (pintype "passive"))
    )
    (net (code "38") (name "/OutA-") (class "Default")
      (node (ref "C30") (pin "2") (pinfunction "2_2") (pintype "passive"))
      (node (ref "M2") (pin "0") (pinfunction "OUT_0") (pintype "passive"))
      (node (ref "M2") (pin "4") (pinfunction "OUT_4") (pintype "passive"))
    )
    (net (code "39") (name "/PCLK") (class "Default")
      (node (ref "U1") (pin "87") (pinfunction "ADC1_SE12/PTB6/FB_AD23_87") (pintype "bidirectional"))
    )
    (net (code "40") (name "/PTA0") (class "Default")
      (node (ref "JLink1") (pin "4") (pinfunction "4_4") (pintype "passive"))
      (node (ref "U1") (pin "50") (pinfunction "JTAG_TCLK/SWD_CLK/EZP_CLK/TSI0_CH1/PTA0/~{UART0_CTS}/FTM0_CH5_50") (pintype "bidirectional"))
    )
    (net (code "41") (name "/PTA1") (class "Default")
      (node (ref "JLink1") (pin "8") (pinfunction "8_8") (pintype "passive"))
      (node (ref "U1") (pin "51") (pinfunction "JTAG_TDI/EZP_DI/TSI0_CH2/PTA1/UART0_RX/FTM0_CH6_51") (pintype "bidirectional"))
    )
    (net (code "42") (name "/PTA2") (class "Default")
      (node (ref "JLink1") (pin "6") (pinfunction "6_6") (pintype "passive"))
      (node (ref "U1") (pin "52") (pinfunction "JTAG_TDO/TRACE_SWO/EZP_DO/TSI0_CH3/PTA2/UART0_TX/FTM0_CH7_52") (pintype "bidirectional"))
    )
    (net (code "43") (name "/PTA3") (class "Default")
      (node (ref "JLink1") (pin "2") (pinfunction "2_2") (pintype "passive"))
      (node (ref "U1") (pin "53") (pinfunction "JTAG_TMS/SWD_DIO/TSI0_CH4/PTA3/~{UART0_RTS}/FTM0_CH0_53") (pintype "bidirectional"))
    )
    (net (code "44") (name "/PTA4") (class "Default")
      (node (ref "U1") (pin "54") (pinfunction "~{NMI}/~{EZP_CS}/TSI0_CH~{5}PTA~{4}FTM0_CH1_54") (pintype "bidirectional"))
    )
    (net (code "45") (name "/PTA5") (class "Default")
      (node (ref "U1") (pin "55") (pinfunction "JTAG_TRST/PTA5/FTM0_CH2/RMII0_RXER/MII0_RXER/CMP2_OUT/I2S0_RX_BCLK_55") (pintype "bidirectional"))
    )
    (net (code "46") (name "/PTA6") (class "Default")
      (node (ref "R1") (pin "1") (pinfunction "1_1") (pintype "passive"))
      (node (ref "R2") (pin "2") (pinfunction "2_2") (pintype "passive"))
      (node (ref "U1") (pin "58") (pinfunction "PTA6/FTM0_CH3/TRACE_CLKOUT_58") (pintype "bidirectional"))
    )
    (net (code "47") (name "/PTA7") (class "Default")
      (node (ref "Servo") (pin "3") (pinfunction "3_3") (pintype "passive"))
      (node (ref "U1") (pin "59") (pinfunction "ADC0_SE10/PTA7/FTM0_CH4/TRACE_D3_59") (pintype "bidirectional"))
    )
    (net (code "48") (name "/PTA8") (class "Default")
      (node (ref "R12") (pin "1") (pinfunction "1_1") (pintype "passive"))
      (node (ref "U1") (pin "60") (pinfunction "ADC0_SE11/PTA8/FTM1_CH0/FTM1_QD_PHA/TRACE_D2_60") (pintype "bidirectional"))
    )
    (net (code "49") (name "/PTA9") (class "Default")
      (node (ref "U1") (pin "61") (pinfunction "PTA9/FTM1_CH1/MII0_RXD3/FTM1_QD_PHB/TRACE_D1_61") (pintype "bidirectional"))
    )
    (net (code "50") (name "/PTA14") (class "Default")
      (node (ref "U1") (pin "66") (pinfunction "PTA14/SPI0_PCS0/UART0_TX/RMII0_CRS_DV/MII0_RXDV/I2S0_TX_BCLK_66") (pintype "bidirectional"))
    )
    (net (code "51") (name "/PTA15") (class "Default")
      (node (ref "U1") (pin "67") (pinfunction "PTA15/SPI0_SCK/UART0_RX/RMII0_TXEN/MII0_TXEN/I2S0_RXD_67") (pintype "bidirectional"))
    )
    (net (code "52") (name "/PTA16") (class "Default")
      (node (ref "U1") (pin "68") (pinfunction "PTA16/SPI0_SOUT/~{UART0_CTS}/RMII0_TXD0/MII0_TXD0/I2S0_RX_FS_68") (pintype "bidirectional"))
    )
    (net (code "53") (name "/PTA17") (class "Default")
      (node (ref "U1") (pin "69") (pinfunction "ADC1_SE17/PTA17/SPI0_SIN/~{UART0_RTS}/RMII0_TXD1/MII0_TXD1/I2S0_MCLK/I2S0_CLKIN_69") (pintype "bidirectional"))
    )
    (net (code "54") (name "/PTA19") (class "Default")
      (node (ref "U1") (pin "73") (pinfunction "XTAL/PTA19/FTM1_FLT0/FTM_CLKIN1/LPT0_ALT1_73") (pintype "bidirectional"))
    )
    (net (code "55") (name "/PTA24") (class "Default")
      (node (ref "U1") (pin "75") (pinfunction "PTA24/MII0_TXD2/FB_A29_75") (pintype "bidirectional"))
    )
    (net (code "56") (name "/PTA25") (class "Default")
      (node (ref "U1") (pin "76") (pinfunction "PTA25/MII0_TXCLK/FB_A28_76") (pintype "bidirectional"))
    )
    (net (code "57") (name "/PTA26") (class "Default")
      (node (ref "U1") (pin "77") (pinfunction "PTA26/MII0_TXD3/FB_A27_77") (pintype "bidirectional"))
    )
    (net (code "58") (name "/PTA27") (class "Default")
      (node (ref "U1") (pin "78") (pinfunction "PTA27/MII0_CRS/FB_A26_78") (pintype "bidirectional"))
    )
    (net (code "59") (name "/PTA29") (class "Default")
      (node (ref "U1") (pin "80") (pinfunction "PTA29/MII0_COL/FB_A24_80") (pintype "bidirectional"))
    )
    (net (code "60") (name "/PTB5") (class "Default")
      (node (ref "U1") (pin "86") (pinfunction "ADC1_SE11/PTB5/ENET0_1588_TMR3/FTM2_FLT0_86") (pintype "bidirectional"))
    )
    (net (code "61") (name "/PTB8") (class "Default")
      (node (ref "U1") (pin "89") (pinfunction "PTB8/~{UART3_RTS}/FB_AD21_89") (pintype "bidirectional"))
    )
    (net (code "62") (name "/PTB9") (class "Default")
      (node (ref "U1") (pin "90") (pinfunction "PTB9/SPI1_PCS1/~{UART3_CTS}/FB_AD20_90") (pintype "bidirectional"))
    )
    (net (code "63") (name "/PTB16") (class "Default")
      (node (ref "U1") (pin "95") (pinfunction "TSI0_CH9/PTB16/SPI1_SOUT/UART0_RX/FB_AD17/EWM_IN_95") (pintype "bidirectional"))
    )
    (net (code "64") (name "/PTB17") (class "Default")
      (node (ref "U1") (pin "96") (pinfunction "TSI0_CH10/PTB17/SPI1_SIN/UART0_TX/FB_AD16/~{EWM_OUT}_96") (pintype "bidirectional"))
    )
    (net (code "65") (name "/PTB18") (class "Default")
      (node (ref "U1") (pin "97") (pinfunction "TSI0_CH11/PTB18/CAN0_TX/FTM2_CH0/I2S0_TX_BCLK/FB_AD15/FTM2_QD_PHA_97") (pintype "bidirectional"))
    )
    (net (code "66") (name "/PTB19") (class "Default")
      (node (ref "U1") (pin "98") (pinfunction "TSI0_CH12/PTB19/CAN0_RX/FTM2_CH1/I2S0_TX_FS/~{FB_OE}/FTM2_QD_PHB_98") (pintype "bidirectional"))
    )
    (net (code "67") (name "/PTB20") (class "Default")
      (node (ref "U1") (pin "99") (pinfunction "PTB20/SPI2_PCS0/FB_AD31/CMP0_OUT_99") (pintype "bidirectional"))
    )
    (net (code "68") (name "/PTB21") (class "Default")
      (node (ref "U1") (pin "100") (pinfunction "PTB21/SPI2_SCK/FB_AD30/CMP1_OUT_100") (pintype "bidirectional"))
    )
    (net (code "69") (name "/PTB22") (class "Default")
      (node (ref "U1") (pin "101") (pinfunction "PTB22/SPI2_SOUT/FB_AD29/CMP2_OUT_101") (pintype "bidirectional"))
    )
    (net (code "70") (name "/PTB23") (class "Default")
      (node (ref "U1") (pin "102") (pinfunction "PTB23/SPI2_SIN/SPI0_PCS5/FB_AD28_102") (pintype "bidirectional"))
    )
    (net (code "71") (name "/PTC0") (class "Default")
      (node (ref "U1") (pin "103") (pinfunction "ADC0_SE14/TSI0_CH13/PTC0/SPI0_PCS4/PDB0_EXTRG/I2S0_TXD/FB_AD14_103") (pintype "bidirectional"))
    )
    (net (code "72") (name "/PTC1") (class "Default")
      (node (ref "U1") (pin "104") (pinfunction "ADC0_SE15/TSI0_CH14/PTC1/SPI0_PCS3/~{UART1_RTS}/FTM0_CH0/FB_AD13_104") (pintype "bidirectional"))
    )
    (net (code "73") (name "/PTC2") (class "Default")
      (node (ref "U1") (pin "105") (pinfunction "ADC0_SE4b/CMP1_IN0/TSI0_CH15/PTC2/SPI0_PCS2/UART1_CTS_b/FTM0_CH1/FB_AD12_105") (pintype "bidirectional"))
    )
    (net (code "74") (name "/PTC3") (class "Default")
      (node (ref "U1") (pin "106") (pinfunction "CMP1_IN1/PTC3/SPI0_PCS1/UART1_RX/FTM0_CH2/FB_CLKOUT_106") (pintype "bidirectional"))
    )
    (net (code "80") (name "/PTC9") (class "Default")
      (node (ref "U1") (pin "114") (pinfunction "ADC1_SE5b/CMP0_IN3/PTC9/I2S0_RX_BCLK/FB_AD6/FTM2_FLT0_114") (pintype "bidirectional"))
    )
    (net (code "81") (name "/PTC10") (class "Default")
      (node (ref "U1") (pin "115") (pinfunction "ADC1_SE6b/CMP0_IN4/PTC10/I2C1_SCL/I2S0_RX_FS/FB_AD5_115") (pintype "bidirectional"))
    )
    (net (code "82") (name "/PTC11") (class "Default")
      (node (ref "U1") (pin "116") (pinfunction "ADC1_SE7b/PTC11/I2C1_SDA/I2S0_RXD/~{FB_RW}_116") (pintype "bidirectional"))
    )
    (net (code "83") (name "/PTC13") (class "Default")
      (node (ref "U1") (pin "118") (pinfunction "PTC13/~{UART4_CTS}/FB_AD26_118") (pintype "bidirectional"))
    )
    (net (code "84") (name "/PTC14") (class "Default")
      (node (ref "U1") (pin "119") (pinfunction "PTC14/UART4_RX/FB_AD25_119") (pintype "bidirectional"))
    )
    (net (code "85") (name "/PTC15") (class "Default")
      (node (ref "U1") (pin "120") (pinfunction "PTC15/UART4_TX/FB_AD24_120") (pintype "bidirectional"))
    )
    (net (code "86") (name "/PTC16") (class "Default")
      (node (ref "U1") (pin "123") (pinfunction "PTC16/CAN1_RX/UART3_RX/ENET0_1588_TMR0/~{FB_CS5}/FB_TSIZ1/~{FB_BE23_16_BLS15_8}_123") (pintype "bidirectional"))
    )
    (net (code "87") (name "/PTC17") (class "Default")
      (node (ref "U1") (pin "124") (pinfunction "PTC17/CAN1_TX/UART3_TX/ENET0_1588_TMR1/~{FB_CS4}/FB_TSIZ0/~{FB_BE31_24_BLS7_0}_124") (pintype "bidirectional"))
    )
    (net (code "88") (name "/PTC18") (class "Default")
      (node (ref "U1") (pin "125") (pinfunction "PTC18/~{UART3_RTS}/ENET0_1588_TMR2/~{FB_TBST}/~{FB_CS2}/~{FB_BE15_8_BLS23_16}_125") (pintype "bidirectional"))
    )
    (net (code "89") (name "/PTC19") (class "Default")
      (node (ref "U1") (pin "126") (pinfunction "PTC19/~{UART3_CTS}/ENET0_1588_TMR3/~{FB_CS3}/~{FB_BE7_0_BLS31_24}/~{FB_TA}_126") (pintype "bidirectional"))
    )
    (net (code "92") (name "/PTD4") (class "Default")
      (node (ref "U1") (pin "131") (pinfunction "PTD4/SPI0_PCS1/~{UART0_RTS}/FTM0_CH4/FB_AD2/EWM_IN_131") (pintype "bidirectional"))
    )
    (net (code "93") (name "/PTD5") (class "Default")
      (node (ref "U1") (pin "132") (pinfunction "ADC0_SE6b/PTD5/SPI0_PCS2/~{UART0_CTS}/FTM0_CH5/FB_AD1/~{EWM_OUT}_132") (pintype "bidirectional"))
    )
    (net (code "94") (name "/PTD6") (class "Default")
      (node (ref "U1") (pin "133") (pinfunction "ADC0_SE7b/PTD6/SPI0_PCS3/UART0_RX/FTM0_CH6/FB_AD0/FTM0_FLT0_133") (pintype "bidirectional"))
    )
    (net (code "95") (name "/PTD7") (class "Default")
      (node (ref "U1") (pin "136") (pinfunction "PTD7/CMT_IRO/UART0_TX/FTM0_CH7/FTM0_FLT1_136") (pintype "bidirectional"))
    )
    (net (code "96") (name "/PTD8") (class "Default")
      (node (ref "U1") (pin "137") (pinfunction "PTD8/I2C0_SCL/UART5_RX/FB_A16_137") (pintype "bidirectional"))
    )
    (net (code "97") (name "/PTD9") (class "Default")
      (node (ref "U1") (pin "138") (pinfunction "PTD9/I2C0_SDA/UART5_TX/FB_A17_138") (pintype "bidirectional"))
    )
    (net (code "98") (name "/PTD10") (class "Default")
      (node (ref "U1") (pin "139") (pinfunction "PTD10/~{UART5_RTS}/FB_A18_139") (pintype "bidirectional"))
    )
    (net (code "99") (name "/PTD11") (class "Default")
      (node (ref "U1") (pin "140") (pinfunction "PTD11/SPI2_PCS0/~{UART5_CTS}/SDHC0_CLKIN/FB_A19_140") (pintype "bidirectional"))
    )
    (net (code "100") (name "/PTD12") (class "Default")
      (node (ref "U1") (pin "141") (pinfunction "PTD12/SPI2_SCK/SDHC0_D4/FB_A20_141") (pintype "bidirectional"))
    )
    (net (code "101") (name "/PTD13") (class "Default")
      (node (ref "U1") (pin "142") (pinfunction "PTD13/SPI2_SOUT/SDHC0_D5/FB_A21_142") (pintype "bidirectional"))
    )
    (net (code "102") (name "/PTD14") (class "Default")
      (node (ref "U1") (pin "143") (pinfunction "PTD14/SPI2_SIN/SDHC0_D6/FB_A22_143") (pintype "bidirectional"))
    )
    (net (code "103") (name "/PTD15") (class "Default")
      (node (ref "U1") (pin "144") (pinfunction "PTD15/SPI2_PCS1/SDHC0_D7/FB_A23_144") (pintype "bidirectional"))
    )
    (net (code "104") (name "/PTE0") (class "Default")
      (node (ref "LCD") (pin "6") (pinfunction "6_6") (pintype "passive"))
      (node (ref "U1") (pin "1") (pinfunction "ADC1_SE4a/PTE0/SPI1_PCS1/UART1_TX/SDHC0_D1/I2C1_SDA_1") (pintype "bidirectional"))
    )
    (net (code "105") (name "/PTE1") (class "Default")
      (node (ref "LCD") (pin "4") (pinfunction "4_4") (pintype "passive"))
      (node (ref "U1") (pin "2") (pinfunction "ADC1_SE5a/PTE1/SPI1_SOUT/UART1_RX/SDHC0_D0/I2C1_SCL_2") (pintype "bidirectional"))
    )
    (net (code "106") (name "/PTE2") (class "Default")
      (node (ref "LCD") (pin "3") (pinfunction "3_3") (pintype "passive"))
      (node (ref "U1") (pin "3") (pinfunction "ADC1_SE6a/PTE2/SPI1_SCK/~{UART1_CTS}/SDHC0_DCLK_3") (pintype "bidirectional"))
    )
    (net (code "107") (name "/PTE3") (class "Default")
      (node (ref "LCD") (pin "5") (pinfunction "5_5") (pintype "passive"))
      (node (ref "U1") (pin "4") (pinfunction "ADC1_SE7a/PTE3/SPI1_SIN/~{UART1_RTS}/SDHC0_CMD_4") (pintype "bidirectional"))
    )
    (net (code "108") (name "/PTE4") (class "Default")
      (node (ref "LCD") (pin "7") (pinfunction "7_7") (pintype "passive"))
      (node (ref "U1") (pin "7") (pinfunction "PTE4/SPI1_PCS0/UART3_TX/SDHC0_D3_7") (pintype "bidirectional"))
    )
    (net (code "109") (name "/PTE5") (class "Default")
      (node (ref "U1") (pin "8") (pinfunction "PTE5/SPI1_PCS2/UART3_RX/SDHC0_D2_8") (pintype "bidirectional"))
    )
    (net (code "110") (name "/PTE6") (class "Default")
      (node (ref "U1") (pin "9") (pinfunction "PTE6/SPI1_PCS3/~{UART3_CTS}/I2S0_MCLK/I2S0_CLKIN_9") (pintype "bidirectional"))
    )
    (net (code "111") (name "/PTE8") (class "Default")
      (node (ref "U1") (pin "11") (pinfunction "PTE8/UART5_TX/I2S0_RX_FS_11") (pintype "bidirectional"))
    )
    (net (code "112") (name "/PTE24") (class "Default")
      (node (ref "BT") (pin "3") (pinfunction "3_3") (pintype "passive"))
      (node (ref "U1") (pin "45") (pinfunction "ADC0_SE17/PTE24/CAN1_TX/UART4_TX/~{EWM_OUT}_45") (pintype "bidirectional"))
    )
    (net (code "113") (name "/PTE25") (class "Default")
      (node (ref "BT") (pin "4") (pinfunction "4_4") (pintype "passive"))
      (node (ref "U1") (pin "46") (pinfunction "ADC0_SE18/PTE25/CAN1_RX/UART4_RX/EWM_IN_46") (pintype "bidirectional"))
    )
    (net (code "114") (name "/PTE26") (class "Default")
      (node (ref "U1") (pin "47") (pinfunction "PTE26/~{UART4_CTS}/ENET_1588_CLKIN/RTC_CLKOUT/USB_CLKIN_47") (pintype "bidirectional"))
    )
    (net (code "115") (name "/PTE27") (class "Default")
      (node (ref "U1") (pin "48") (pinfunction "PTE27/~{UART4_RTS}_48") (pintype "bidirectional"))
    )
    (net (code "116") (name "/PTE28") (class "Default")
      (node (ref "U1") (pin "49") (pinfunction "PTE28_49") (pintype "bidirectional"))
    )
    (net (code "117") (name "/RESET") (class "Default")
      (node (ref "C21") (pin "2") (pinfunction "2_2") (pintype "passive"))
      (node (ref "JLink1") (pin "10") (pinfunction "10_10") (pintype "passive"))
      (node (ref "R20") (pin "2") (pinfunction "2_2") (pintype "passive"))
      (node (ref "RESET1") (pin "2") (pinfunction "NO_2") (pintype "passive"))
      (node (ref "U1") (pin "74") (pinfunction "~{RESET}_74") (pintype "bidirectional"))
    )
    (net (code "118") (name "/USB0R_DM") (class "Default")
      (node (ref "U1") (pin "20") (pinfunction "USB0_DM_20") (pintype "bidirectional"))
    )
    (net (code "119") (name "/USB0R_DP") (class "Default")
      (node (ref "U1") (pin "19") (pinfunction "USB0_DP_19") (pintype "bidirectional"))
    )
    (net (code "120") (name "/VBAT") (class "Default")
      (node (ref "U1") (pin "42") (pinfunction "VBAT_42") (pintype "power_in"))
    )
    (net (code "121") (name "/VREF OUT") (class "Default")
      (node (ref "C12") (pin "2") (pinfunction "2_2") (pintype "passive"))
      (node (ref "U1") (pin "37") (pinfunction "VREF_OUT_37") (pintype "power_in"))
    )
    (net (code "122") (name "8V") (class "Default")
      (node (ref "C26") (pin "2") (pinfunction "2_2") (pintype "passive"))
      (node (ref "C27") (pin "2") (pinfunction "2_2") (pintype "passive"))
      (node (ref "C32") (pin "1") (pinfunction "1_1") (pintype "passive"))
      (node (ref "C34") (pin "1") (pinfunction "1_1") (pintype "passive"))
      (node (ref "F1") (pin "2") (pinfunction "2_2") (pintype "passive"))
      (node (ref "IC1") (pin "1") (pinfunction "V_in_1") (pintype "output"))
      (node (ref "LM2") (pin "3") (pinfunction "IN_3") (pintype "power_in"))
      (node (ref "M1") (pin "7") (pinfunction "VS_7") (pintype "power_in"))
      (node (ref "M2") (pin "7") (pinfunction "VS_7") (pintype "power_in"))
      (node (ref "R1") (pin "2") (pinfunction "2_2") (pintype "passive"))
    )
    (net (code "123") (name "A3V3") (class "Default")
      (node (ref "C10") (pin "2") (pinfunction "2_2") (pintype "passive"))
      (node (ref "L1") (pin "1") (pinfunction "1_1") (pintype "passive"))
      (node (ref "L4") (pin "2") (pinfunction "2_2") (pintype "passive"))
      (node (ref "U1") (pin "31") (pinfunction "VDDA_31") (pintype "power_in"))
    )
    (net (code "124") (name "AGND") (class "Default")
      (node (ref "C10") (pin "1") (pinfunction "1_1") (pintype "passive"))
      (node (ref "C12") (pin "1") (pinfunction "1_1") (pintype "passive"))
      (node (ref "L2") (pin "1") (pinfunction "1_1") (pintype "passive"))
      (node (ref "L3") (pin "2") (pinfunction "2_2") (pintype "passive"))
      (node (ref "U1") (pin "34") (pinfunction "VSSA_34") (pintype "power_in"))
    )
    (net (code "125") (name "GND") (class "Default")
      (node (ref "BT") (pin "2") (pinfunction "2_2") (pintype "passive"))
      (node (ref "C1") (pin "1") (pinfunction "1_1") (pintype "passive"))
      (node (ref "C15") (pin "1") (pinfunction "1_1") (pintype "passive"))
      (node (ref "C16") (pin "1") (pinfunction "1_1") (pintype "passive"))
      (node (ref "C2") (pin "1") (pinfunction "1_1") (pintype "passive"))
      (node (ref "C20") (pin "2") (pinfunction "2_2") (pintype "passive"))
      (node (ref "C21") (pin "1") (pinfunction "1_1") (pintype "passive"))
      (node (ref "C22") (pin "1") (pinfunction "1_1") (pintype "passive"))
      (node (ref "C23") (pin "1") (pinfunction "1_1") (pintype "passive"))
      (node (ref "C24") (pin "1") (pinfunction "1_1") (pintype "passive"))
      (node (ref "C25") (pin "1") (pinfunction "1_1") (pintype "passive"))
      (node (ref "C26") (pin "1") (pinfunction "1_1") (pintype "passive"))
      (node (ref "C27") (pin "1") (pinfunction "1_1") (pintype "passive"))
      (node (ref "C28") (pin "1") (pinfunction "1_1") (pintype "passive"))
      (node (ref "C29") (pin "1") (pinfunction "1_1") (pintype "passive"))
      (node (ref "C3") (pin "1") (pinfunction "1_1") (pintype "passive"))
      (node (ref "C31") (pin "2") (pinfunction "2_2") (pintype "passive"))
      (node (ref "C32") (pin "2") (pinfunction "2_2") (pintype "passive"))
      (node (ref "C34") (pin "2") (pinfunction "2_2") (pintype "passive"))
      (node (ref "C4") (pin "1") (pinfunction "1_1") (pintype "passive"))
      (node (ref "C5") (pin "1") (pinfunction "1_1") (pintype "passive"))
      (node (ref "C6") (pin "1") (pinfunction "1_1") (pintype "passive"))
      (node (ref "C7") (pin "1") (pinfunction "1_1") (pintype "passive"))
      (node (ref "C8") (pin "1") (pinfunction "1_1") (pintype "passive"))
      (node (ref "C9") (pin "1") (pinfunction "1_1") (pintype "passive"))
      (node (ref "CCD1") (pin "5") (pinfunction "5_5") (pintype "passive"))
      (node (ref "CCD2") (pin "5") (pinfunction "5_5") (pintype "passive"))
      (node (ref "D6") (pin "1") (pinfunction "A_1") (pintype "passive"))
      (node (ref "ENCODER1") (pin "4") (pinfunction "4_4") (pintype "passive"))
      (node (ref "GND") (pin "1") (pinfunction "1_1") (pintype "passive"))
      (node (ref "GND") (pin "2") (pinfunction "2_2") (pintype "passive"))
      (node (ref "GND") (pin "3") (pinfunction "3_3") (pintype "passive"))
      (node (ref "IC1") (pin "3") (pinfunction "GND_3") (pintype "passive"))
      (node (ref "IC1") (pin "5") (pinfunction "SD_5") (pintype "passive"))
      (node (ref "IMU") (pin "2") (pinfunction "2_2") (pintype "passive"))
      (node (ref "JLink1") (pin "3") (pinfunction "3_3") (pintype "passive"))
      (node (ref "JLink1") (pin "5") (pinfunction "5_5") (pintype "passive"))
      (node (ref "JLink1") (pin "7") (pinfunction "7_7") (pintype "passive"))
      (node (ref "JLink1") (pin "9") (pinfunction "9_9") (pintype "passive"))
      (node (ref "JP") (pin "2") (pinfunction "2_2") (pintype "passive"))
      (node (ref "L3") (pin "1") (pinfunction "1_1") (pintype "passive"))
      (node (ref "LCD") (pin "1") (pinfunction "1_1") (pintype "passive"))
      (node (ref "LM1") (pin "1") (pinfunction "GND_1") (pintype "power_in"))
      (node (ref "LM2") (pin "1") (pinfunction "GND_1") (pintype "power_in"))
      (node (ref "Min") (pin "4") (pinfunction "4_4") (pintype "passive"))
      (node (ref "Mout") (pin "4") (pinfunction "4_4") (pintype "passive"))
      (node (ref "NPN1") (pin "1") (pinfunction "E_1") (pintype "passive"))
      (node (ref "R10") (pin "1") (pinfunction "1_1") (pintype "passive"))
      (node (ref "R2") (pin "1") (pinfunction "1_1") (pintype "passive"))
      (node (ref "R23") (pin "2") (pinfunction "2_2") (pintype "passive"))
      (node (ref "R30") (pin "2") (pinfunction "2_2") (pintype "passive"))
      (node (ref "R33") (pin "1") (pinfunction "1_1") (pintype "passive"))
      (node (ref "R34") (pin "1") (pinfunction "1_1") (pintype "passive"))
      (node (ref "R36") (pin "1") (pinfunction "1_1") (pintype "passive"))
      (node (ref "R38") (pin "1") (pinfunction "1_1") (pintype "passive"))
      (node (ref "R7") (pin "1") (pinfunction "1_1") (pintype "passive"))
      (node (ref "RESET1") (pin "1") (pinfunction "COMMON_1") (pintype "passive"))
      (node (ref "SW1") (pin "1") (pinfunction "COMMON_1") (pintype "passive"))
      (node (ref "SW2") (pin "1") (pinfunction "COMMON_1") (pintype "passive"))
      (node (ref "Servo") (pin "1") (pinfunction "1_1") (pintype "passive"))
      (node (ref "U1") (pin "107") (pinfunction "VSS4_107") (pintype "power_in"))
      (node (ref "U1") (pin "121") (pinfunction "VSS10_121") (pintype "power_in"))
      (node (ref "U1") (pin "134") (pinfunction "VSS7_134") (pintype "power_in"))
      (node (ref "U1") (pin "17") (pinfunction "VSS2_17") (pintype "power_in"))
      (node (ref "U1") (pin "18") (pinfunction "VSS8_18") (pintype "power_in"))
      (node (ref "U1") (pin "44") (pinfunction "VSS9_44") (pintype "power_in"))
      (node (ref "U1") (pin "57") (pinfunction "VSS5_57") (pintype "power_in"))
      (node (ref "U1") (pin "6") (pinfunction "VSS1_6") (pintype "power_in"))
      (node (ref "U1") (pin "71") (pinfunction "VSS6_71") (pintype "power_in"))
      (node (ref "U1") (pin "93") (pinfunction "VSS3_93") (pintype "power_in"))
      (node (ref "Y1") (pin "2") (pinfunction "GND_2") (pintype "power_in"))
    )
    (net (code "126") (name "MCU_33V") (class "Default")
      (node (ref "C1") (pin "2") (pinfunction "2_2") (pintype "passive"))
      (node (ref "C2") (pin "2") (pinfunction "2_2") (pintype "passive"))
      (node (ref "C28") (pin "2") (pinfunction "2_2") (pintype "passive"))
      (node (ref "C29") (pin "2") (pinfunction "2_2") (pintype "passive"))
      (node (ref "C3") (pin "2") (pinfunction "2_2") (pintype "passive"))
      (node (ref "C4") (pin "2") (pinfunction "2_2") (pintype "passive"))
      (node (ref "C5") (pin "2") (pinfunction "2_2") (pintype "passive"))
      (node (ref "C6") (pin "2") (pinfunction "2_2") (pintype "passive"))
      (node (ref "C7") (pin "2") (pinfunction "2_2") (pintype "passive"))
      (node (ref "C8") (pin "2") (pinfunction "2_2") (pintype "passive"))
      (node (ref "C9") (pin "2") (pinfunction "2_2") (pintype "passive"))
      (node (ref "D5") (pin "1") (pinfunction "A_1") (pintype "passive"))
      (node (ref "JLink1") (pin "1") (pinfunction "1_1") (pintype "passive"))
      (node (ref "L4") (pin "1") (pinfunction "1_1") (pintype "passive"))
      (node (ref "L5") (pin "1") (pinfunction "1_1") (pintype "passive"))
      (node (ref "LM2") (pin "2") (pinfunction "OUT_2") (pintype "power_in"))
      (node (ref "LM2") (pin "4") (pinfunction "TAB_4") (pintype "power_in"))
      (node (ref "R21") (pin "2") (pinfunction "2_2") (pintype "passive"))
      (node (ref "U1") (pin "108") (pinfunction "VDD7_108") (pintype "power_in"))
      (node (ref "U1") (pin "122") (pinfunction "VDD8_122") (pintype "power_in"))
      (node (ref "U1") (pin "135") (pinfunction "VDD9_135") (pintype "power_in"))
      (node (ref "U1") (pin "16") (pinfunction "VDD2_16") (pintype "power_in"))
      (node (ref "U1") (pin "43") (pinfunction "VDD6_43") (pintype "power_in"))
      (node (ref "U1") (pin "5") (pinfunction "VDD1_5") (pintype "power_in"))
      (node (ref "U1") (pin "56") (pinfunction "VDD3_56") (pintype "power_in"))
      (node (ref "U1") (pin "70") (pinfunction "VDD4_70") (pintype "power_in"))
      (node (ref "U1") (pin "94") (pinfunction "VDD5_94") (pintype "power_in"))
    )
    (net (code "127") (name "MIGND") (class "Default")
      (node (ref "M1") (pin "1") (pinfunction "GND_1") (pintype "power_in"))
      (node (ref "M2") (pin "1") (pinfunction "GND_1") (pintype "power_in"))
      (node (ref "R25") (pin "1") (pinfunction "1_1") (pintype "passive"))
      (node (ref "R26") (pin "1") (pinfunction "1_1") (pintype "passive"))
      (node (ref "R33") (pin "2") (pinfunction "2_2") (pintype "passive"))
      (node (ref "R34") (pin "2") (pinfunction "2_2") (pintype "passive"))
      (node (ref "R36") (pin "2") (pinfunction "2_2") (pintype "passive"))
      (node (ref "R38") (pin "2") (pinfunction "2_2") (pintype "passive"))
    )
    (net (code "128") (name "Net-(B1-Pad1)") (class "Default")
      (node (ref "B1") (pin "1") (pinfunction "1_1") (pintype "passive"))
      (node (ref "R6") (pin "1") (pinfunction "1_1") (pintype "passive"))
    )
    (net (code "129") (name "Net-(D1-A)") (class "Default")
      (node (ref "D1") (pin "1") (pinfunction "A_1") (pintype "passive"))
      (node (ref "R3") (pin "1") (pinfunction "1_1") (pintype "passive"))
    )
    (net (code "130") (name "Net-(D2-A)") (class "Default")
      (node (ref "D2") (pin "1") (pinfunction "A_1") (pintype "passive"))
      (node (ref "R4") (pin "1") (pinfunction "1_1") (pintype "passive"))
    )
    (net (code "131") (name "Net-(D3-A)") (class "Default")
      (node (ref "D3") (pin "1") (pinfunction "A_1") (pintype "passive"))
      (node (ref "R5") (pin "1") (pinfunction "1_1") (pintype "passive"))
    )
    (net (code "132") (name "Net-(D3-K)") (class "Default")
      (node (ref "D3") (pin "2") (pinfunction "K_2") (pintype "passive"))
      (node (ref "IR1") (pin "2") (pinfunction "2_2") (pintype "passive"))
    )
    (net (code "133") (name "Net-(D4-A)") (class "Default")
      (node (ref "D4") (pin "1") (pinfunction "A_1") (pintype "passive"))
      (node (ref "R8") (pin "1") (pinfunction "1_1") (pintype "passive"))
    )
    (net (code "134") (name "Net-(D4-K)") (class "Default")
      (node (ref "D4") (pin "2") (pinfunction "K_2") (pintype "passive"))
      (node (ref "IR2") (pin "2") (pinfunction "2_2") (pintype "passive"))
    )
    (net (code "135") (name "Net-(D5-K)") (class "Default")
      (node (ref "D5") (pin "2") (pinfunction "K_2") (pintype "passive"))
      (node (ref "R23") (pin "1") (pinfunction "1_1") (pintype "passive"))
    )
    (net (code "136") (name "Net-(D6-K)") (class "Default")
      (node (ref "D6") (pin "2") (pinfunction "K_2") (pintype "passive"))
      (node (ref "IC1") (pin "2") (pinfunction "V_out_2") (pintype "input"))
      (node (ref "L6") (pin "2") (pinfunction "2_2") (pintype "passive"))
    )
    (net (code "137") (name "Net-(IC1-FB)") (class "Default")
      (node (ref "IC1") (pin "4") (pinfunction "FB_4") (pintype "passive"))
      (node (ref "R29") (pin "2") (pinfunction "2_2") (pintype "passive"))
      (node (ref "R30") (pin "1") (pinfunction "1_1") (pintype "passive"))
    )
    (net (code "138") (name "Net-(M1-SR)") (class "Default")
      (node (ref "M1") (pin "5") (pinfunction "SR_5") (pintype "passive"))
      (node (ref "R25") (pin "2") (pinfunction "2_2") (pintype "passive"))
    )
    (net (code "139") (name "Net-(M2-SR)") (class "Default")
      (node (ref "M2") (pin "5") (pinfunction "SR_5") (pintype "passive"))
      (node (ref "R26") (pin "2") (pinfunction "2_2") (pintype "passive"))
    )
    (net (code "140") (name "Net-(NPN1-B)") (class "Default")
      (node (ref "NPN1") (pin "2") (pinfunction "B_2") (pintype "passive"))
      (node (ref "R12") (pin "2") (pinfunction "2_2") (pintype "passive"))
    )
    (net (code "141") (name "Net-(NPN1-C)") (class "Default")
      (node (ref "NPN1") (pin "3") (pinfunction "C_3") (pintype "passive"))
      (node (ref "R6") (pin "2") (pinfunction "2_2") (pintype "passive"))
    )
    (net (code "142") (name "Net-(U1-VREFH)") (class "Default")
      (node (ref "C11") (pin "2") (pinfunction "2_2") (pintype "passive"))
      (node (ref "L1") (pin "2") (pinfunction "2_2") (pintype "passive"))
      (node (ref "U1") (pin "32") (pinfunction "VREFH_32") (pintype "power_in"))
    )
    (net (code "143") (name "Net-(U1-VREFL)") (class "Default")
      (node (ref "C11") (pin "1") (pinfunction "1_1") (pintype "passive"))
      (node (ref "L2") (pin "2") (pinfunction "2_2") (pintype "passive"))
      (node (ref "U1") (pin "33") (pinfunction "VREFL_33") (pintype "power_in"))
    )
    (net (code "144") (name "Net-(Y1-OE)") (class "Default")
      (node (ref "R21") (pin "1") (pinfunction "1_1") (pintype "passive"))
      (node (ref "Y1") (pin "1") (pinfunction "OE_1") (pintype "input"))
    )
    (net (code "145") (name "Net-(Y1-VDD)") (class "Default")
      (node (ref "C20") (pin "1") (pinfunction "1_1") (pintype "passive"))
      (node (ref "L5") (pin "2") (pinfunction "2_2") (pintype "passive"))
      (node (ref "Y1") (pin "4") (pinfunction "VDD_4") (pintype "power_in"))
    )
    (net (code "146") (name "VCC_5V") (class "Default")
      (node (ref "5v") (pin "1") (pinfunction "1_1") (pintype "passive"))
      (node (ref "5v") (pin "2") (pinfunction "2_2") (pintype "passive"))
      (node (ref "5v") (pin "3") (pinfunction "3_3") (pintype "passive"))
      (node (ref "B1") (pin "2") (pinfunction "2_2") (pintype "passive"))
      (node (ref "BT") (pin "1") (pinfunction "1_1") (pintype "passive"))
      (node (ref "C22") (pin "2") (pinfunction "2_2") (pintype "passive"))
      (node (ref "C23") (pin "2") (pinfunction "2_2") (pintype "passive"))
      (node (ref "C31") (pin "1") (pinfunction "1_1") (pintype "passive"))
      (node (ref "L6") (pin "1") (pinfunction "1_1") (pintype "passive"))
      (node (ref "LM1") (pin "3") (pinfunction "IN_3") (pintype "power_in"))
      (node (ref "R29") (pin "1") (pinfunction "1_1") (pintype "passive"))
      (node (ref "Servo") (pin "2") (pinfunction "2_2") (pintype "passive"))
    )
    (net (code "147") (name "VCC_33V") (class "Default")
      (node (ref "3.3v") (pin "1") (pinfunction "1_1") (pintype "passive"))
      (node (ref "3.3v") (pin "2") (pinfunction "2_2") (pintype "passive"))
      (node (ref "3.3v") (pin "3") (pinfunction "3_3") (pintype "passive"))
      (node (ref "C24") (pin "2") (pinfunction "2_2") (pintype "passive"))
      (node (ref "C25") (pin "2") (pinfunction "2_2") (pintype "passive"))
      (node (ref "CCD1") (pin "1") (pinfunction "1_1") (pintype "passive"))
      (node (ref "CCD2") (pin "1") (pinfunction "1_1") (pintype "passive"))
      (node (ref "ENCODER1") (pin "1") (pinfunction "1_1") (pintype "passive"))
      (node (ref "IMU") (pin "1") (pinfunction "1_1") (pintype "passive"))
      (node (ref "LCD") (pin "2") (pinfunction "2_2") (pintype "passive"))
      (node (ref "LM1") (pin "2") (pinfunction "OUT_2") (pintype "power_in"))
      (node (ref "LM1") (pin "4") (pinfunction "TAB_4") (pintype "power_in"))
      (node (ref "M1") (pin "3") (pinfunction "INH_3") (pintype "passive"))
      (node (ref "M2") (pin "3") (pinfunction "INH_3") (pintype "passive"))
      (node (ref "Min") (pin "1") (pinfunction "1_1") (pintype "passive"))
      (node (ref "Mout") (pin "1") (pinfunction "1_1") (pintype "passive"))
      (node (ref "R13") (pin "1") (pinfunction "1_1") (pintype "passive"))
      (node (ref "R15") (pin "1") (pinfunction "1_1") (pintype "passive"))
      (node (ref "R20") (pin "1") (pinfunction "1_1") (pintype "passive"))
      (node (ref "R22") (pin "2") (pinfunction "2_2") (pintype "passive"))
      (node (ref "R24") (pin "2") (pinfunction "2_2") (pintype "passive"))
      (node (ref "R3") (pin "2") (pinfunction "2_2") (pintype "passive"))
      (node (ref "R4") (pin "2") (pinfunction "2_2") (pintype "passive"))
      (node (ref "R5") (pin "2") (pinfunction "2_2") (pintype "passive"))
      (node (ref "R8") (pin "2") (pinfunction "2_2") (pintype "passive"))
    )
    (net (code "148") (name "VCC_BAT") (class "Default")
      (node (ref "JP") (pin "1") (pinfunction "1_1") (pintype "passive"))
      (node (ref "Power") (pin "2") (pinfunction "Common_2") (pintype "passive"))
      (node (ref "Power") (pin "3") (pinfunction "PowerIN_3") (pintype "passive"))
    )
    (net (code "149") (name "VCC_BATON") (class "Default")
      (node (ref "F1") (pin "1") (pinfunction "1_1") (pintype "passive"))
      (node (ref "Power") (pin "1") (pinfunction "PowerOUT_1") (pintype "passive"))
    )
    (net (code "150") (name "unconnected-(IR1-Pad1)") (class "Default")
      (node (ref "IR1") (pin "1") (pinfunction "1_1") (pintype "passive"))
    )
    (net (code "151") (name "unconnected-(IR2-Pad1)") (class "Default")
      (node (ref "IR2") (pin "1") (pinfunction "1_1") (pintype "passive"))
    )
    (net (code "152") (name "unconnected-(M1-IS-Pad6)") (class "Default")
      (node (ref "M1") (pin "6") (pinfunction "IS_6") (pintype "passive+no_connect"))
    )
    (net (code "153") (name "unconnected-(M2-IS-Pad6)") (class "Default")
      (node (ref "M2") (pin "6") (pinfunction "IS_6") (pintype "passive+no_connect"))
    )
    (net (code "154") (name "unconnected-(Min-Pad2)") (class "Default")
      (node (ref "Min") (pin "2") (pinfunction "2_2") (pintype "passive"))
    )
    (net (code "155") (name "unconnected-(Min-Pad3)") (class "Default")
      (node (ref "Min") (pin "3") (pinfunction "3_3") (pintype "passive"))
    )
    (net (code "156") (name "unconnected-(U1-ADC1_SE4b{slash}CMP0_IN2{slash}PTC8{slash}I2S0_MCLK{slash}I2S0_CLKIN{slash}FB_AD7-Pad113)") (class "Default")
      (node (ref "U1") (pin "113") (pinfunction "ADC1_SE4b/CMP0_IN2/PTC8/I2S0_MCLK/I2S0_CLKIN/FB_AD7_113") (pintype "bidirectional"))
    )
    (net (code "157") (name "unconnected-(U1-CMP0_IN0{slash}PTC6{slash}SPI0_SOUT{slash}PDB0_EXTRG{slash}FB_AD9-Pad111)") (class "Default")
      (node (ref "U1") (pin "111") (pinfunction "CMP0_IN0/PTC6/SPI0_SOUT/PDB0_EXTRG/FB_AD9_111") (pintype "bidirectional"))
    )
    (net (code "158") (name "unconnected-(U1-CMP0_IN1{slash}PTC7{slash}SPI0_SIN{slash}FB_AD8-Pad112)") (class "Default")
      (node (ref "U1") (pin "112") (pinfunction "CMP0_IN1/PTC7/SPI0_SIN/FB_AD8_112") (pintype "bidirectional"))
    )
    (net (code "159") (name "unconnected-(U1-EXTAL32-Pad41)") (class "Default")
      (node (ref "U1") (pin "41") (pinfunction "EXTAL32_41") (pintype "input+no_connect"))
    )
    (net (code "160") (name "unconnected-(U1-PTC4{slash}SPI0_PCS0{slash}UART1_TX{slash}FTM0_CH3{slash}FB_AD11{slash}CMP1_OUT-Pad109)") (class "Default")
      (node (ref "U1") (pin "109") (pinfunction "PTC4/SPI0_PCS0/UART1_TX/FTM0_CH3/FB_AD11/CMP1_OUT_109") (pintype "bidirectional"))
    )
    (net (code "161") (name "unconnected-(U1-PTC5{slash}SPI0_SCK{slash}LPT0_ALT2{slash}FB_AD10{slash}CMP0_OUT-Pad110)") (class "Default")
      (node (ref "U1") (pin "110") (pinfunction "PTC5/SPI0_SCK/LPT0_ALT2/FB_AD10/CMP0_OUT_110") (pintype "bidirectional"))
    )
    (net (code "162") (name "unconnected-(U1-PTD2{slash}SPI0_SOUT{slash}UART2_RX{slash}FB_AD4-Pad129)") (class "Default")
      (node (ref "U1") (pin "129") (pinfunction "PTD2/SPI0_SOUT/UART2_RX/FB_AD4_129") (pintype "bidirectional"))
    )
    (net (code "163") (name "unconnected-(U1-PTD3{slash}SPI0_SIN{slash}UART2_TX{slash}FB_AD3-Pad130)") (class "Default")
      (node (ref "U1") (pin "130") (pinfunction "PTD3/SPI0_SIN/UART2_TX/FB_AD3_130") (pintype "bidirectional"))
    )
    (net (code "164") (name "unconnected-(U1-VOUT33-Pad21)") (class "Default")
      (node (ref "U1") (pin "21") (pinfunction "VOUT33_21") (pintype "power_in+no_connect"))
    )
    (net (code "165") (name "unconnected-(U1-VREGIN-Pad22)") (class "Default")
      (node (ref "U1") (pin "22") (pinfunction "VREGIN_22") (pintype "power_in+no_connect"))
    )
    (net (code "166") (name "unconnected-(U1-XTAL32-Pad40)") (class "Default")
      (node (ref "U1") (pin "40") (pinfunction "XTAL32_40") (pintype "output+no_connect"))
    )
  )
)
